# CPU_LPC1776_SUP_PROG.net
KiCad netlist of a schematic drawn in Altium Designer
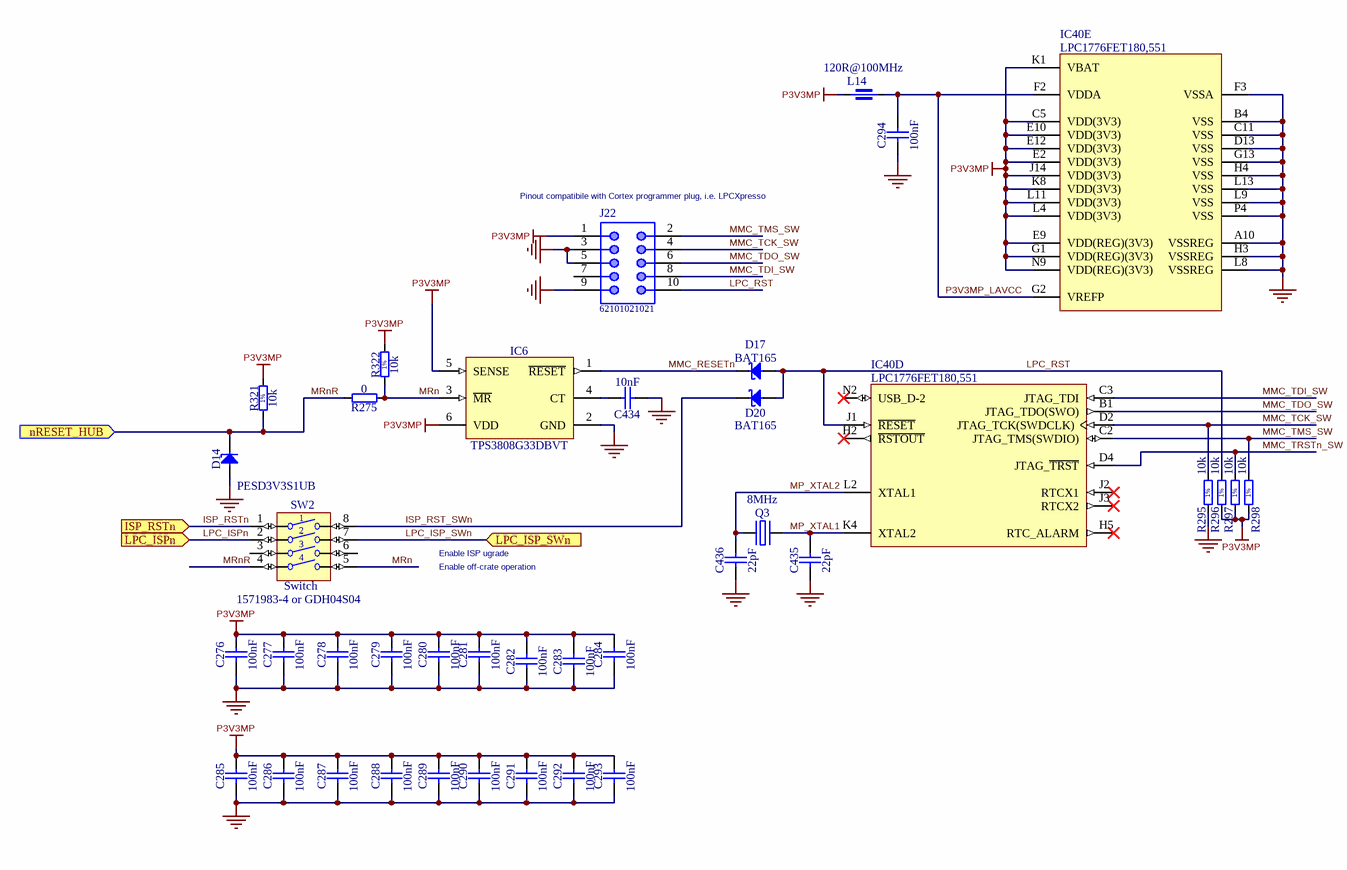
[diagram p0: CPU_LPC1776_SUP_PROG.SchDoc]

(export (version "E")
  (design (tool "Eeschema 10.0.6"))
  (components
    (comp (ref "C276")
      (value "100nF")
      (footprint "CAPC0603X33N")
      (description "Non-polarised capacitor")
      (fields
        (field (name "MANUFACTURER PART NUMBER") "CC0201_100NF_6.3V_10%_X5R")
        (field (name "MANUFACTURER") "GENERIC")
        (field (name "AUTHOR") "CERN DEM JLC")
      )
      (libsource (lib "Capacitors") (part "Capacitor - non polarized"))
    )
    (comp (ref "C277")
      (value "100nF")
      (footprint "CAPC0603X33N")
      (description "Non-polarised capacitor")
      (fields
        (field (name "MANUFACTURER PART NUMBER") "CC0201_100NF_6.3V_10%_X5R")
        (field (name "MANUFACTURER") "GENERIC")
        (field (name "AUTHOR") "CERN DEM JLC")
      )
      (libsource (lib "Capacitors") (part "Capacitor - non polarized"))
    )
    (comp (ref "C278")
      (value "100nF")
      (footprint "CAPC0603X33N")
      (description "Non-polarised capacitor")
      (fields
        (field (name "MANUFACTURER PART NUMBER") "CC0201_100NF_6.3V_10%_X5R")
        (field (name "MANUFACTURER") "GENERIC")
        (field (name "AUTHOR") "CERN DEM JLC")
      )
      (libsource (lib "Capacitors") (part "Capacitor - non polarized"))
    )
    (comp (ref "C279")
      (value "100nF")
      (footprint "CAPC0603X33N")
      (description "Non-polarised capacitor")
      (fields
        (field (name "MANUFACTURER PART NUMBER") "CC0201_100NF_6.3V_10%_X5R")
        (field (name "MANUFACTURER") "GENERIC")
        (field (name "AUTHOR") "CERN DEM JLC")
      )
      (libsource (lib "Capacitors") (part "Capacitor - non polarized"))
    )
    (comp (ref "C280")
      (value "100nF")
      (footprint "CAPC0603X33N")
      (description "Non-polarised capacitor")
      (fields
        (field (name "MANUFACTURER PART NUMBER") "CC0201_100NF_6.3V_10%_X5R")
        (field (name "MANUFACTURER") "GENERIC")
        (field (name "AUTHOR") "CERN DEM JLC")
      )
      (libsource (lib "Capacitors") (part "Capacitor - non polarized"))
    )
    (comp (ref "C281")
      (value "100nF")
      (footprint "CAPC0603X33N")
      (description "Non-polarised capacitor")
      (fields
        (field (name "MANUFACTURER PART NUMBER") "CC0201_100NF_6.3V_10%_X5R")
        (field (name "MANUFACTURER") "GENERIC")
        (field (name "AUTHOR") "CERN DEM JLC")
      )
      (libsource (lib "Capacitors") (part "Capacitor - non polarized"))
    )
    (comp (ref "C282")
      (value "100nF")
      (footprint "CAPC0603X33N")
      (description "Non-polarised capacitor")
      (fields
        (field (name "MANUFACTURER PART NUMBER") "CC0201_100NF_6.3V_10%_X5R")
        (field (name "MANUFACTURER") "GENERIC")
        (field (name "AUTHOR") "CERN DEM JLC")
      )
      (libsource (lib "Capacitors") (part "Capacitor - non polarized"))
    )
    (comp (ref "C283")
      (value "100nF")
      (footprint "CAPC0603X33N")
      (description "Non-polarised capacitor")
      (fields
        (field (name "MANUFACTURER PART NUMBER") "CC0201_100NF_6.3V_10%_X5R")
        (field (name "MANUFACTURER") "GENERIC")
        (field (name "AUTHOR") "CERN DEM JLC")
      )
      (libsource (lib "Capacitors") (part "Capacitor - non polarized"))
    )
    (comp (ref "C284")
      (value "100nF")
      (footprint "CAPC0603X33N")
      (description "Non-polarised capacitor")
      (fields
        (field (name "MANUFACTURER PART NUMBER") "CC0201_100NF_6.3V_10%_X5R")
        (field (name "MANUFACTURER") "GENERIC")
        (field (name "AUTHOR") "CERN DEM JLC")
      )
      (libsource (lib "Capacitors") (part "Capacitor - non polarized"))
    )
    (comp (ref "C285")
      (value "100nF")
      (footprint "CAPC0603X33N")
      (description "Non-polarised capacitor")
      (fields
        (field (name "MANUFACTURER PART NUMBER") "CC0201_100NF_6.3V_10%_X5R")
        (field (name "MANUFACTURER") "GENERIC")
        (field (name "AUTHOR") "CERN DEM JLC")
      )
      (libsource (lib "Capacitors") (part "Capacitor - non polarized"))
    )
    (comp (ref "C286")
      (value "100nF")
      (footprint "CAPC0603X33N")
      (description "Non-polarised capacitor")
      (fields
        (field (name "MANUFACTURER PART NUMBER") "CC0201_100NF_6.3V_10%_X5R")
        (field (name "MANUFACTURER") "GENERIC")
        (field (name "AUTHOR") "CERN DEM JLC")
      )
      (libsource (lib "Capacitors") (part "Capacitor - non polarized"))
    )
    (comp (ref "C287")
      (value "100nF")
      (footprint "CAPC0603X33N")
      (description "Non-polarised capacitor")
      (fields
        (field (name "MANUFACTURER PART NUMBER") "CC0201_100NF_6.3V_10%_X5R")
        (field (name "MANUFACTURER") "GENERIC")
        (field (name "AUTHOR") "CERN DEM JLC")
      )
      (libsource (lib "Capacitors") (part "Capacitor - non polarized"))
    )
    (comp (ref "C288")
      (value "100nF")
      (footprint "CAPC0603X33N")
      (description "Non-polarised capacitor")
      (fields
        (field (name "MANUFACTURER PART NUMBER") "CC0201_100NF_6.3V_10%_X5R")
        (field (name "MANUFACTURER") "GENERIC")
        (field (name "AUTHOR") "CERN DEM JLC")
      )
      (libsource (lib "Capacitors") (part "Capacitor - non polarized"))
    )
    (comp (ref "C289")
      (value "100nF")
      (footprint "CAPC0603X33N")
      (description "Non-polarised capacitor")
      (fields
        (field (name "MANUFACTURER PART NUMBER") "CC0201_100NF_6.3V_10%_X5R")
        (field (name "MANUFACTURER") "GENERIC")
        (field (name "AUTHOR") "CERN DEM JLC")
      )
      (libsource (lib "Capacitors") (part "Capacitor - non polarized"))
    )
    (comp (ref "C290")
      (value "100nF")
      (footprint "CAPC0603X33N")
      (description "Non-polarised capacitor")
      (fields
        (field (name "MANUFACTURER PART NUMBER") "CC0201_100NF_6.3V_10%_X5R")
        (field (name "MANUFACTURER") "GENERIC")
        (field (name "AUTHOR") "CERN DEM JLC")
      )
      (libsource (lib "Capacitors") (part "Capacitor - non polarized"))
    )
    (comp (ref "C291")
      (value "100nF")
      (footprint "CAPC0603X33N")
      (description "Non-polarised capacitor")
      (fields
        (field (name "MANUFACTURER PART NUMBER") "CC0201_100NF_6.3V_10%_X5R")
        (field (name "MANUFACTURER") "GENERIC")
        (field (name "AUTHOR") "CERN DEM JLC")
      )
      (libsource (lib "Capacitors") (part "Capacitor - non polarized"))
    )
    (comp (ref "C292")
      (value "100nF")
      (footprint "CAPC0603X33N")
      (description "Non-polarised capacitor")
      (fields
        (field (name "MANUFACTURER PART NUMBER") "CC0201_100NF_6.3V_10%_X5R")
        (field (name "MANUFACTURER") "GENERIC")
        (field (name "AUTHOR") "CERN DEM JLC")
      )
      (libsource (lib "Capacitors") (part "Capacitor - non polarized"))
    )
    (comp (ref "C293")
      (value "100nF")
      (footprint "CAPC0603X33N")
      (description "Non-polarised capacitor")
      (fields
        (field (name "MANUFACTURER PART NUMBER") "CC0201_100NF_6.3V_10%_X5R")
        (field (name "MANUFACTURER") "GENERIC")
        (field (name "AUTHOR") "CERN DEM JLC")
      )
      (libsource (lib "Capacitors") (part "Capacitor - non polarized"))
    )
    (comp (ref "C294")
      (value "100nF")
      (footprint "CAPC0603X33N")
      (description "Non-polarised capacitor")
      (fields
        (field (name "MANUFACTURER PART NUMBER") "CC0201_100NF_6.3V_10%_X5R")
        (field (name "MANUFACTURER") "GENERIC")
        (field (name "AUTHOR") "CERN DEM JLC")
      )
      (libsource (lib "Capacitors") (part "Capacitor - non polarized"))
    )
    (comp (ref "C434")
      (value "10nF")
      (footprint "CAPC1005X55N")
      (description "Non-polarised capacitor")
      (fields
        (field (name "MANUFACTURER PART NUMBER") "CC0402_10NF_16V_10%_X7R")
        (field (name "MANUFACTURER") "GENERIC")
        (field (name "AUTHOR") "CERN DEM JLC")
      )
      (libsource (lib "Capacitors") (part "Capacitor - non polarized"))
    )
    (comp (ref "C435")
      (value "22pF")
      (footprint "CAPC1005X55N")
      (description "Non-polarised capacitor")
      (fields
        (field (name "MANUFACTURER PART NUMBER") "CC0402_22PF_50V_5%_C0G")
        (field (name "MANUFACTURER") "GENERIC")
        (field (name "AUTHOR") "CERN DEM JLC")
      )
      (libsource (lib "Capacitors") (part "Capacitor - non polarized"))
    )
    (comp (ref "C436")
      (value "22pF")
      (footprint "CAPC1005X55N")
      (description "Non-polarised capacitor")
      (fields
        (field (name "MANUFACTURER PART NUMBER") "CC0402_22PF_50V_5%_C0G")
        (field (name "MANUFACTURER") "GENERIC")
        (field (name "AUTHOR") "CERN DEM JLC")
      )
      (libsource (lib "Capacitors") (part "Capacitor - non polarized"))
    )
    (comp (ref "D14")
      (value "PESD3V3S1UB")
      (footprint "SODFL1608X65N")
      (description "ESD protection diode")
      (fields
        (field (name "MANUFACTURER") "NXP SEMICONDUCTORS")
        (field (name "VOLTAGE") "3V3")
        (field (name "AUTHOR") "CERN DEM JLC")
      )
      (libsource (lib "ICs And Semiconductors") (part "Diode ESD"))
    )
    (comp (ref "D17")
      (value "BAT165")
      (footprint "SOD2512X110N")
      (description "Schottky Diode")
      (fields
        (field (name "MANUFACTURER") "INFINEON")
        (field (name "VOLTAGE") "40V")
        (field (name "AUTHOR") "CERN DEM JLC")
      )
      (libsource (lib "ICs And Semiconductors") (part "Diode Schottky"))
    )
    (comp (ref "D20")
      (value "BAT165")
      (footprint "SOD2512X110N")
      (description "Schottky Diode")
      (fields
        (field (name "MANUFACTURER") "INFINEON")
        (field (name "VOLTAGE") "40V")
        (field (name "AUTHOR") "CERN DEM JLC")
      )
      (libsource (lib "ICs And Semiconductors") (part "Diode Schottky"))
    )
    (comp (ref "IC6")
      (value "TPS3808G33DBVT")
      (footprint "SOT95P280X145-6N")
      (description "Low Quiescent Current, Programmable-Delay Supervisory Circuit")
      (fields (field (name "MANUFACTURER") "TEXAS INSTRUMENTS") (field (name "AUTHOR") "CERN DEM JLC"))
      (libsource (lib "ICs And Semiconductors") (part "TPS3808xxxDBV"))
    )
    (comp (ref "IC40")
      (value "LPC1776FET180,551")
      (footprint "BGA180C80P14X14_1200X1200X120")
      (fields (field (name "MANUFACTURER") "NXP SEMICONDUCTORS") (field (name "AUTHOR") "CERN DEM JMW"))
      (libsource (lib "ICs And Semiconductors") (part "LPC1776FET180,551"))
    )
    (comp (ref "J22")
      (value "62101021021")
      (footprint "62101021021")
      (description "SMT Vertical Pin Header WR-PHD, Pitch 1.27 mm, Dual Row, 10 pins")
      (fields (field (name "PUBLISHER") "Wurth Elektronik"))
      (libsource (lib "ALTIUM-WR-PHD_PIN_HEADER-rev18b") (part "62101021021"))
    )
    (comp (ref "L14")
      (value "120R@100MHz")
      (footprint "INDC1608X95N")
      (fields
        (field (name "MANUFACTURER PART NUMBER") "BLM18PG121SN1D")
        (field (name "MANUFACTURER") "MURATA")
        (field (name "PART NUMBER") "IND0603_MURATA_BLM18PG121SN1D")
        (field (name "AUTHOR") "CERN DEM BC")
      )
      (libsource (lib "Inductors & Transformers") (part "Ferrite Bead"))
    )
    (comp (ref "Q3")
      (value "8MHz")
      (footprint "XTAL_TXC_7A")
      (description "Quartz Crystal")
      (fields
        (field (name "MANUFACTURER PART NUMBER") "7A-8.000MAAE-T")
        (field (name "MANUFACTURER") "TXC CORPORATION")
        (field (name "AUTHOR") "CERN DEM JLC")
      )
      (libsource (lib "ICs And Semiconductors") (part "Quartz Crystal"))
    )
    (comp (ref "R275")
      (value "0")
      (footprint "RESC1005X40N")
      (description "Resistor")
      (fields
        (field (name "MANUFACTURER PART NUMBER") "R0402_0R_JUMPER")
        (field (name "MANUFACTURER") "GENERIC")
        (field (name "AUTHOR") "CERN DEM JLC")
      )
      (libsource (lib "Resistors") (part "Resistor"))
    )
    (comp (ref "R295")
      (value "10k")
      (footprint "RESC1005X40N")
      (description "Resistor - 1%")
      (fields
        (field (name "MANUFACTURER PART NUMBER") "R0402_10K_1%_0.0625W_100PPM")
        (field (name "MANUFACTURER") "GENERIC")
        (field (name "AUTHOR") "CERN DEM JLC")
      )
      (libsource (lib "Resistors") (part "Resistor - 1%"))
    )
    (comp (ref "R296")
      (value "10k")
      (footprint "RESC1005X40N")
      (description "Resistor - 1%")
      (fields
        (field (name "MANUFACTURER PART NUMBER") "R0402_10K_1%_0.0625W_100PPM")
        (field (name "MANUFACTURER") "GENERIC")
        (field (name "AUTHOR") "CERN DEM JLC")
      )
      (libsource (lib "Resistors") (part "Resistor - 1%"))
    )
    (comp (ref "R297")
      (value "10k")
      (footprint "RESC1005X40N")
      (description "Resistor - 1%")
      (fields
        (field (name "MANUFACTURER PART NUMBER") "R0402_10K_1%_0.0625W_100PPM")
        (field (name "MANUFACTURER") "GENERIC")
        (field (name "AUTHOR") "CERN DEM JLC")
      )
      (libsource (lib "Resistors") (part "Resistor - 1%"))
    )
    (comp (ref "R298")
      (value "10k")
      (footprint "RESC1005X40N")
      (description "Resistor - 1%")
      (fields
        (field (name "MANUFACTURER PART NUMBER") "R0402_10K_1%_0.0625W_100PPM")
        (field (name "MANUFACTURER") "GENERIC")
        (field (name "AUTHOR") "CERN DEM JLC")
      )
      (libsource (lib "Resistors") (part "Resistor - 1%"))
    )
    (comp (ref "R321")
      (value "10k")
      (footprint "RESC1005X40N")
      (description "Resistor - 1%")
      (fields
        (field (name "MANUFACTURER PART NUMBER") "R0402_10K_1%_0.0625W_100PPM")
        (field (name "MANUFACTURER") "GENERIC")
        (field (name "AUTHOR") "CERN DEM JLC")
      )
      (libsource (lib "Resistors") (part "Resistor - 1%"))
    )
    (comp (ref "R322")
      (value "10k")
      (footprint "RESC1005X40N")
      (description "Resistor - 1%")
      (fields
        (field (name "MANUFACTURER PART NUMBER") "R0402_10K_1%_0.0625W_100PPM")
        (field (name "MANUFACTURER") "GENERIC")
        (field (name "AUTHOR") "CERN DEM JLC")
      )
      (libsource (lib "Resistors") (part "Resistor - 1%"))
    )
    (comp (ref "SW2")
      (value "Switch")
      (footprint "SW_TYCO_1571983-4")
      (description "4 Ways SPST DIP Switch")
      (fields
        (field (name "MANUFACTURER PART NUMBER") "1571983-4 or GDH04S04")
        (field (name "MANUFACTURER") "TYCO")
        (field (name "PART NUMBER") "SW_TYCO_1571983-4")
        (field (name "AUTHOR") "CERN DEM JLC")
      )
      (libsource (lib "Eletro-mechanical") (part "SW 4x SPST DIP Switch"))
    )
  )
  (nets
    (net (code "1") (name "/ISP_RST_SWn") (class "Default")
      (node (ref "D20") (pin "1") (pinfunction "C_1") (pintype "passive"))
      (node (ref "SW2") (pin "8") (pinfunction "8_8") (pintype "bidirectional"))
    )
    (net (code "2") (name "/ISP_RSTn") (class "Default")
      (node (ref "SW2") (pin "1") (pinfunction "1_1") (pintype "bidirectional"))
    )
    (net (code "3") (name "/LPC_ISP_SWn") (class "Default")
      (node (ref "SW2") (pin "7") (pinfunction "7_7") (pintype "bidirectional"))
    )
    (net (code "4") (name "/LPC_ISPn") (class "Default")
      (node (ref "SW2") (pin "2") (pinfunction "2_2") (pintype "bidirectional"))
    )
    (net (code "5") (name "/LPC_RST") (class "Default")
      (node (ref "D17") (pin "2") (pinfunction "A_2") (pintype "passive"))
      (node (ref "D20") (pin "2") (pinfunction "A_2") (pintype "passive"))
      (node (ref "IC40") (pin "J1") (pinfunction "~{RESET}_J1") (pintype "input"))
      (node (ref "J22") (pin "10") (pinfunction "10_10") (pintype "passive"))
      (node (ref "R296") (pin "2") (pinfunction "2_2") (pintype "passive"))
    )
    (net (code "6") (name "/MMC_RESETn") (class "Default")
      (node (ref "D17") (pin "1") (pinfunction "C_1") (pintype "passive"))
      (node (ref "IC6") (pin "1") (pinfunction "~{RESET}_1") (pintype "output"))
    )
    (net (code "7") (name "/MMC_TCK_SW") (class "Default")
      (node (ref "IC40") (pin "D2") (pinfunction "JTAG_TCK(SWDCLK)_D2") (pintype "input"))
      (node (ref "J22") (pin "4") (pinfunction "4_4") (pintype "passive"))
      (node (ref "R295") (pin "2") (pinfunction "2_2") (pintype "passive"))
    )
    (net (code "8") (name "/MMC_TDI_SW") (class "Default")
      (node (ref "IC40") (pin "C3") (pinfunction "JTAG_TDI_C3") (pintype "input"))
      (node (ref "J22") (pin "8") (pinfunction "8_8") (pintype "passive"))
    )
    (net (code "9") (name "/MMC_TDO_SW") (class "Default")
      (node (ref "IC40") (pin "B1") (pinfunction "JTAG_TDO(SWO)_B1") (pintype "output"))
      (node (ref "J22") (pin "6") (pinfunction "6_6") (pintype "passive"))
    )
    (net (code "10") (name "/MMC_TMS_SW") (class "Default")
      (node (ref "IC40") (pin "C2") (pinfunction "JTAG_TMS(SWDIO)_C2") (pintype "bidirectional"))
      (node (ref "J22") (pin "2") (pinfunction "2_2") (pintype "passive"))
      (node (ref "R298") (pin "2") (pinfunction "2_2") (pintype "passive"))
    )
    (net (code "11") (name "/MMC_TRSTn_SW") (class "Default")
      (node (ref "IC40") (pin "D4") (pinfunction "JTAG_~{TRST}_D4") (pintype "input"))
      (node (ref "R297") (pin "2") (pinfunction "2_2") (pintype "passive"))
    )
    (net (code "12") (name "/MP_XTAL1") (class "Default")
      (node (ref "C435") (pin "2") (pinfunction "2_2") (pintype "passive"))
      (node (ref "IC40") (pin "K4") (pinfunction "XTAL2_K4") (pintype "passive"))
      (node (ref "Q3") (pin "2") (pinfunction "OSC2_2") (pintype "passive"))
    )
    (net (code "13") (name "/MP_XTAL2") (class "Default")
      (node (ref "C436") (pin "2") (pinfunction "2_2") (pintype "passive"))
      (node (ref "IC40") (pin "L2") (pinfunction "XTAL1_L2") (pintype "passive"))
      (node (ref "Q3") (pin "1") (pinfunction "OSC1_1") (pintype "passive"))
    )
    (net (code "14") (name "/MRn") (class "Default")
      (node (ref "IC6") (pin "3") (pinfunction "~{MR}_3") (pintype "input"))
      (node (ref "R275") (pin "1") (pinfunction "1_1") (pintype "passive"))
      (node (ref "R322") (pin "1") (pinfunction "1_1") (pintype "passive"))
      (node (ref "SW2") (pin "5") (pinfunction "5_5") (pintype "bidirectional"))
    )
    (net (code "15") (name "/MRnR") (class "Default")
      (node (ref "D14") (pin "1") (pinfunction "C_1") (pintype "passive"))
      (node (ref "R275") (pin "2") (pinfunction "2_2") (pintype "passive"))
      (node (ref "R321") (pin "1") (pinfunction "1_1") (pintype "passive"))
      (node (ref "SW2") (pin "4") (pinfunction "4_4") (pintype "bidirectional"))
    )
    (net (code "16") (name "/P3V3MP_LAVCC") (class "Default")
      (node (ref "C294") (pin "1") (pinfunction "1_1") (pintype "passive"))
      (node (ref "IC40") (pin "F2") (pinfunction "VDDA_F2") (pintype "power_in"))
      (node (ref "IC40") (pin "G2") (pinfunction "VREFP_G2") (pintype "power_in"))
      (node (ref "L14") (pin "1") (pinfunction "1_1") (pintype "passive"))
    )
    (net (code "17") (name "GND") (class "Default")
      (node (ref "C276") (pin "2") (pinfunction "2_2") (pintype "passive"))
      (node (ref "C277") (pin "2") (pinfunction "2_2") (pintype "passive"))
      (node (ref "C278") (pin "2") (pinfunction "2_2") (pintype "passive"))
      (node (ref "C279") (pin "2") (pinfunction "2_2") (pintype "passive"))
      (node (ref "C280") (pin "2") (pinfunction "2_2") (pintype "passive"))
      (node (ref "C281") (pin "2") (pinfunction "2_2") (pintype "passive"))
      (node (ref "C282") (pin "2") (pinfunction "2_2") (pintype "passive"))
      (node (ref "C283") (pin "2") (pinfunction "2_2") (pintype "passive"))
      (node (ref "C284") (pin "2") (pinfunction "2_2") (pintype "passive"))
      (node (ref "C285") (pin "2") (pinfunction "2_2") (pintype "passive"))
      (node (ref "C286") (pin "2") (pinfunction "2_2") (pintype "passive"))
      (node (ref "C287") (pin "2") (pinfunction "2_2") (pintype "passive"))
      (node (ref "C288") (pin "2") (pinfunction "2_2") (pintype "passive"))
      (node (ref "C289") (pin "2") (pinfunction "2_2") (pintype "passive"))
      (node (ref "C290") (pin "2") (pinfunction "2_2") (pintype "passive"))
      (node (ref "C291") (pin "2") (pinfunction "2_2") (pintype "passive"))
      (node (ref "C292") (pin "2") (pinfunction "2_2") (pintype "passive"))
      (node (ref "C293") (pin "2") (pinfunction "2_2") (pintype "passive"))
      (node (ref "C294") (pin "2") (pinfunction "2_2") (pintype "passive"))
      (node (ref "C434") (pin "1") (pinfunction "1_1") (pintype "passive"))
      (node (ref "C435") (pin "1") (pinfunction "1_1") (pintype "passive"))
      (node (ref "C436") (pin "1") (pinfunction "1_1") (pintype "passive"))
      (node (ref "D14") (pin "2") (pinfunction "A_2") (pintype "passive"))
      (node (ref "IC40") (pin "A10") (pinfunction "VSSREG_A10") (pintype "power_in"))
      (node (ref "IC40") (pin "B4") (pinfunction "VSS_B4") (pintype "power_in"))
      (node (ref "IC40") (pin "C11") (pinfunction "VSS_C11") (pintype "power_in"))
      (node (ref "IC40") (pin "D13") (pinfunction "VSS_D13") (pintype "power_in"))
      (node (ref "IC40") (pin "F3") (pinfunction "VSSA_F3") (pintype "power_in"))
      (node (ref "IC40") (pin "G13") (pinfunction "VSS_G13") (pintype "power_in"))
      (node (ref "IC40") (pin "H3") (pinfunction "VSSREG_H3") (pintype "power_in"))
      (node (ref "IC40") (pin "H4") (pinfunction "VSS_H4") (pintype "power_in"))
      (node (ref "IC40") (pin "L13") (pinfunction "VSS_L13") (pintype "power_in"))
      (node (ref "IC40") (pin "L8") (pinfunction "VSSREG_L8") (pintype "power_in"))
      (node (ref "IC40") (pin "L9") (pinfunction "VSS_L9") (pintype "power_in"))
      (node (ref "IC40") (pin "P4") (pinfunction "VSS_P4") (pintype "power_in"))
      (node (ref "IC6") (pin "2") (pinfunction "GND_2") (pintype "power_in"))
      (node (ref "J22") (pin "3") (pinfunction "3_3") (pintype "passive"))
      (node (ref "J22") (pin "5") (pinfunction "5_5") (pintype "passive"))
      (node (ref "J22") (pin "9") (pinfunction "9_9") (pintype "passive"))
      (node (ref "R295") (pin "1") (pinfunction "1_1") (pintype "passive"))
    )
    (net (code "18") (name "Net-(IC6-CT)") (class "Default")
      (node (ref "C434") (pin "2") (pinfunction "2_2") (pintype "passive"))
      (node (ref "IC6") (pin "4") (pinfunction "CT_4") (pintype "passive"))
    )
    (net (code "19") (name "P3V3MP") (class "Default")
      (node (ref "C276") (pin "1") (pinfunction "1_1") (pintype "passive"))
      (node (ref "C277") (pin "1") (pinfunction "1_1") (pintype "passive"))
      (node (ref "C278") (pin "1") (pinfunction "1_1") (pintype "passive"))
      (node (ref "C279") (pin "1") (pinfunction "1_1") (pintype "passive"))
      (node (ref "C280") (pin "1") (pinfunction "1_1") (pintype "passive"))
      (node (ref "C281") (pin "1") (pinfunction "1_1") (pintype "passive"))
      (node (ref "C282") (pin "1") (pinfunction "1_1") (pintype "passive"))
      (node (ref "C283") (pin "1") (pinfunction "1_1") (pintype "passive"))
      (node (ref "C284") (pin "1") (pinfunction "1_1") (pintype "passive"))
      (node (ref "C285") (pin "1") (pinfunction "1_1") (pintype "passive"))
      (node (ref "C286") (pin "1") (pinfunction "1_1") (pintype "passive"))
      (node (ref "C287") (pin "1") (pinfunction "1_1") (pintype "passive"))
      (node (ref "C288") (pin "1") (pinfunction "1_1") (pintype "passive"))
      (node (ref "C289") (pin "1") (pinfunction "1_1") (pintype "passive"))
      (node (ref "C290") (pin "1") (pinfunction "1_1") (pintype "passive"))
      (node (ref "C291") (pin "1") (pinfunction "1_1") (pintype "passive"))
      (node (ref "C292") (pin "1") (pinfunction "1_1") (pintype "passive"))
      (node (ref "C293") (pin "1") (pinfunction "1_1") (pintype "passive"))
      (node (ref "IC40") (pin "C5") (pinfunction "VDD(3V3)_C5") (pintype "power_in"))
      (node (ref "IC40") (pin "E10") (pinfunction "VDD(3V3)_E10") (pintype "power_in"))
      (node (ref "IC40") (pin "E12") (pinfunction "VDD(3V3)_E12") (pintype "power_in"))
      (node (ref "IC40") (pin "E2") (pinfunction "VDD(3V3)_E2") (pintype "power_in"))
      (node (ref "IC40") (pin "E9") (pinfunction "VDD(REG)(3V3)_E9") (pintype "power_in"))
      (node (ref "IC40") (pin "G1") (pinfunction "VDD(REG)(3V3)_G1") (pintype "power_in"))
      (node (ref "IC40") (pin "J14") (pinfunction "VDD(3V3)_J14") (pintype "power_in"))
      (node (ref "IC40") (pin "K1") (pinfunction "VBAT_K1") (pintype "power_in"))
      (node (ref "IC40") (pin "K8") (pinfunction "VDD(3V3)_K8") (pintype "power_in"))
      (node (ref "IC40") (pin "L11") (pinfunction "VDD(3V3)_L11") (pintype "power_in"))
      (node (ref "IC40") (pin "L4") (pinfunction "VDD(3V3)_L4") (pintype "power_in"))
      (node (ref "IC40") (pin "N9") (pinfunction "VDD(REG)(3V3)_N9") (pintype "power_in"))
      (node (ref "IC6") (pin "5") (pinfunction "SENSE_5") (pintype "input"))
      (node (ref "IC6") (pin "6") (pinfunction "VDD_6") (pintype "power_in"))
      (node (ref "J22") (pin "1") (pinfunction "1_1") (pintype "passive"))
      (node (ref "L14") (pin "2") (pinfunction "2_2") (pintype "passive"))
      (node (ref "R296") (pin "1") (pinfunction "1_1") (pintype "passive"))
      (node (ref "R297") (pin "1") (pinfunction "1_1") (pintype "passive"))
      (node (ref "R298") (pin "1") (pinfunction "1_1") (pintype "passive"))
      (node (ref "R321") (pin "2") (pinfunction "2_2") (pintype "passive"))
      (node (ref "R322") (pin "2") (pinfunction "2_2") (pintype "passive"))
    )
    (net (code "20") (name "unconnected-(IC40D-RTCX1-PadJ2)") (class "Default")
      (node (ref "IC40") (pin "J2") (pinfunction "RTCX1_J2") (pintype "input+no_connect"))
    )
    (net (code "21") (name "unconnected-(IC40D-RTCX2-PadJ3)") (class "Default")
      (node (ref "IC40") (pin "J3") (pinfunction "RTCX2_J3") (pintype "output+no_connect"))
    )
    (net (code "22") (name "unconnected-(IC40D-RTC_ALARM-PadH5)") (class "Default")
      (node (ref "IC40") (pin "H5") (pinfunction "RTC_ALARM_H5") (pintype "output+no_connect"))
    )
    (net (code "23") (name "unconnected-(IC40D-USB_D-2-PadN2)") (class "Default")
      (node (ref "IC40") (pin "N2") (pinfunction "USB_D-2_N2") (pintype "bidirectional+no_connect"))
    )
    (net (code "24") (name "unconnected-(IC40D-~{RSTOUT}-PadH2)") (class "Default")
      (node (ref "IC40") (pin "H2") (pinfunction "~{RSTOUT}_H2") (pintype "output+no_connect"))
    )
    (net (code "25") (name "unconnected-(J22-Pad7)") (class "Default")
      (node (ref "J22") (pin "7") (pinfunction "7_7") (pintype "passive"))
    )
    (net (code "26") (name "unconnected-(SW2-Pad3)") (class "Default")
      (node (ref "SW2") (pin "3") (pinfunction "3_3") (pintype "bidirectional"))
    )
    (net (code "27") (name "unconnected-(SW2-Pad6)") (class "Default")
      (node (ref "SW2") (pin "6") (pinfunction "6_6") (pintype "bidirectional"))
    )
  )
)
